# solar_switch.net
KiCad netlist of a schematic drawn in EAGLE
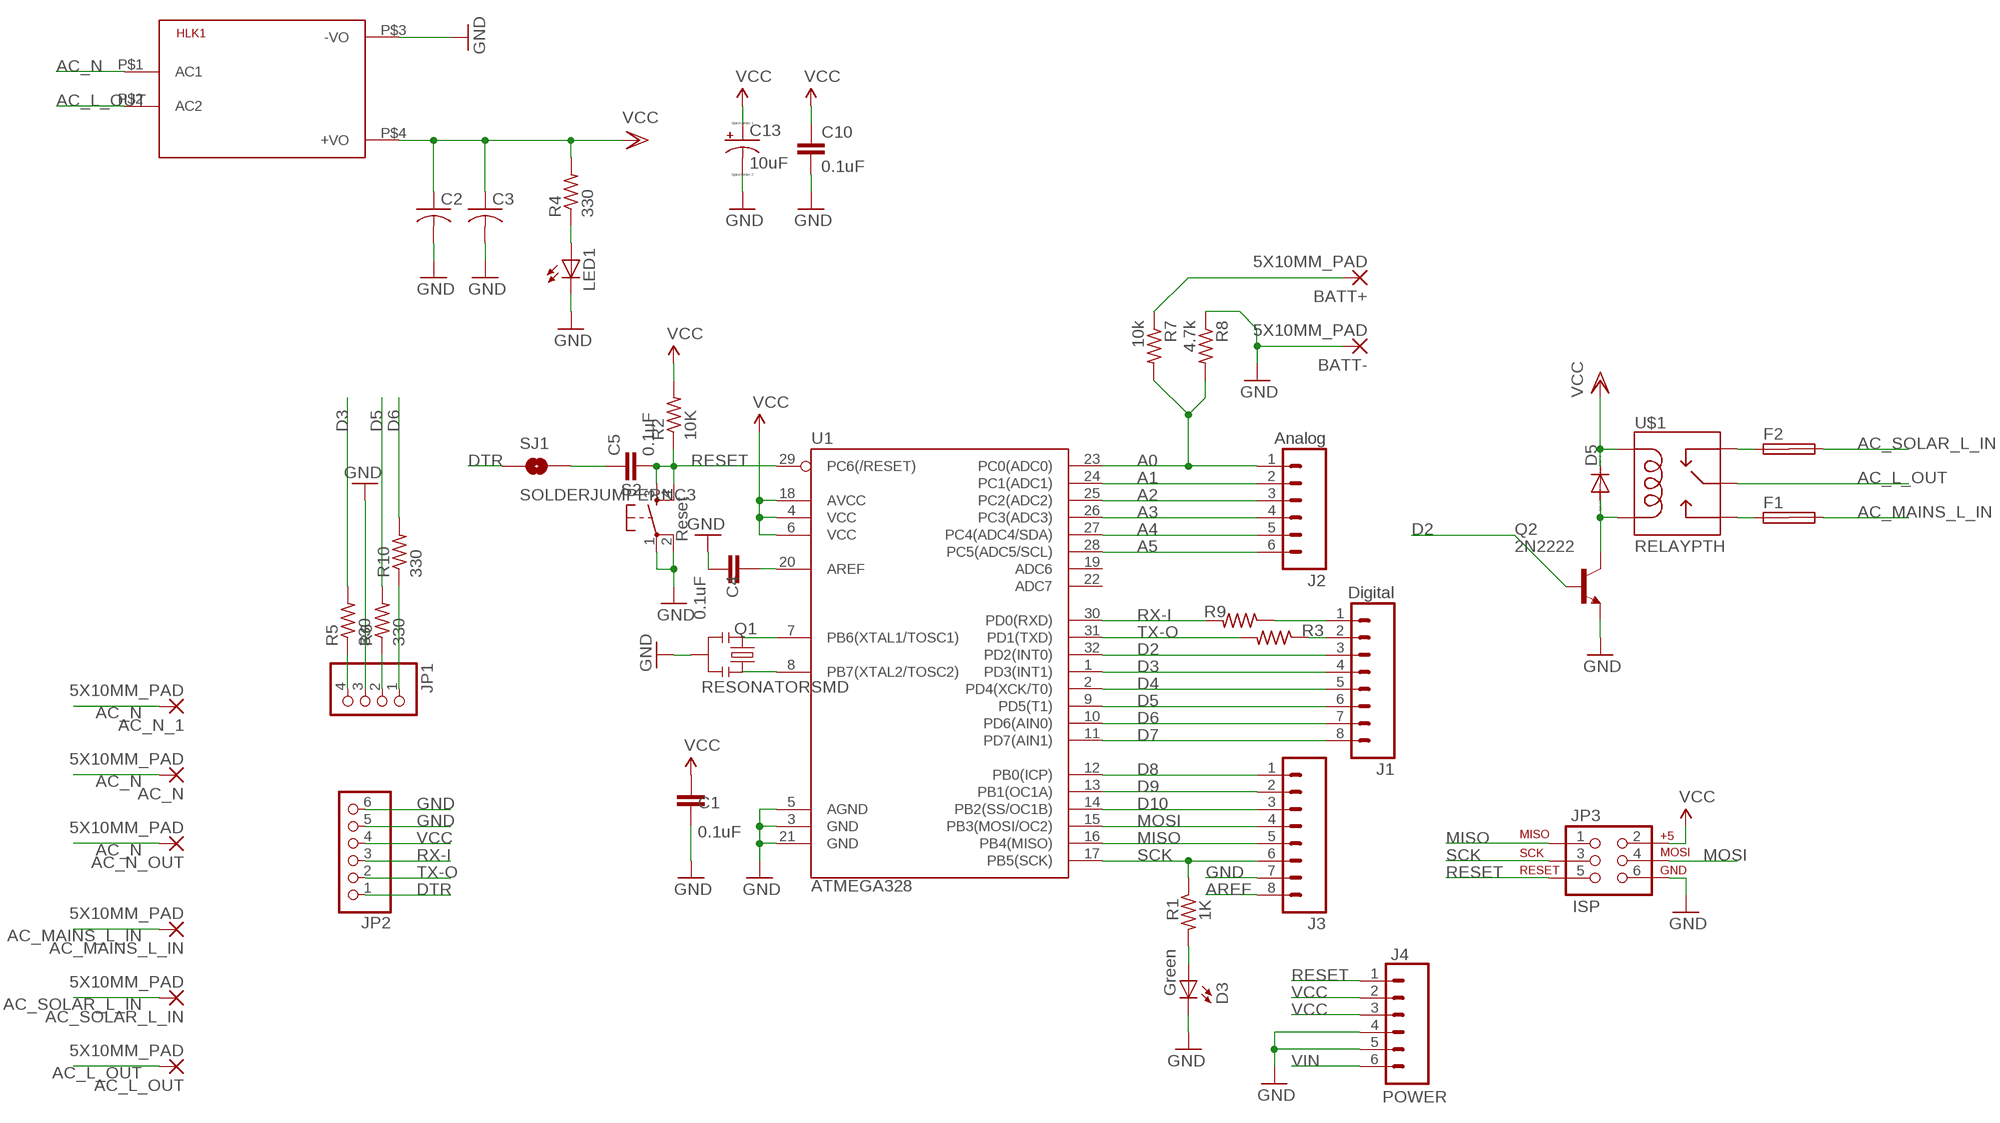
[diagram p0: schematic, sheet 1]

(export (version "E")
  (design (tool "Eeschema 10.0.6"))
  (components
    (comp (ref "AC_L_OUT")
      (value "5X10MM_PAD")
      (footprint "eagle-import:SMD5-10")
      (libsource (lib "eagle-import") (part "5X10MM_PAD"))
    )
    (comp (ref "AC_MAINS_L_IN")
      (value "5X10MM_PAD")
      (footprint "eagle-import:SMD5-10")
      (libsource (lib "eagle-import") (part "5X10MM_PAD"))
    )
    (comp (ref "AC_N")
      (value "5X10MM_PAD")
      (footprint "eagle-import:SMD5-10")
      (libsource (lib "eagle-import") (part "5X10MM_PAD"))
    )
    (comp (ref "AC_N_1")
      (value "5X10MM_PAD")
      (footprint "eagle-import:SMD5-10")
      (libsource (lib "eagle-import") (part "5X10MM_PAD"))
    )
    (comp (ref "AC_N_OUT")
      (value "5X10MM_PAD")
      (footprint "eagle-import:SMD5-10")
      (libsource (lib "eagle-import") (part "5X10MM_PAD"))
    )
    (comp (ref "AC_SOLAR_L_IN")
      (value "5X10MM_PAD")
      (footprint "eagle-import:SMD5-10")
      (libsource (lib "eagle-import") (part "5X10MM_PAD"))
    )
    (comp (ref "BATT+")
      (value "5X10MM_PAD")
      (footprint "eagle-import:SMD5-10")
      (libsource (lib "eagle-import") (part "5X10MM_PAD"))
    )
    (comp (ref "BATT-")
      (value "5X10MM_PAD")
      (footprint "eagle-import:SMD5-10")
      (libsource (lib "eagle-import") (part "5X10MM_PAD"))
    )
    (comp (ref "C1")
      (value "0.1uF")
      (footprint "eagle-import:C0805")
      (libsource (lib "eagle-import") (part "C-EUC0805"))
    )
    (comp (ref "C2")
      (value "C-USC0805K")
      (footprint "eagle-import:C0805K")
      (libsource (lib "eagle-import") (part "C-USC0805K"))
    )
    (comp (ref "C3")
      (value "C-USC0805K")
      (footprint "eagle-import:C0805K")
      (libsource (lib "eagle-import") (part "C-USC0805K"))
    )
    (comp (ref "C4")
      (value "0.1uF")
      (footprint "eagle-import:C0805")
      (libsource (lib "eagle-import") (part "C-EUC0805"))
    )
    (comp (ref "C5")
      (value "0.1uF")
      (footprint "eagle-import:C0805")
      (libsource (lib "eagle-import") (part "C-EUC0805"))
    )
    (comp (ref "C10")
      (value "0.1uF")
      (footprint "eagle-import:C0805")
      (libsource (lib "eagle-import") (part "rcl_334_C-EUC0805"))
    )
    (comp (ref "C13")
      (value "10uF")
      (footprint "eagle-import:PANASONIC_B")
      (libsource (lib "eagle-import") (part "CPOL-USB"))
    )
    (comp (ref "D3")
      (value "Green")
      (footprint "eagle-import:CHIP-LED0805")
      (libsource (lib "eagle-import") (part "LEDCHIP-LED0805"))
    )
    (comp (ref "D5")
      (value "1N4004")
      (footprint "eagle-import:DO41-10")
      (libsource (lib "eagle-import") (part "1N4004"))
    )
    (comp (ref "F1")
      (value "SHKOG")
      (footprint "eagle-import:SHKOG")
      (libsource (lib "eagle-import") (part "SHKOG"))
    )
    (comp (ref "F2")
      (value "SHKOG")
      (footprint "eagle-import:SHKOG")
      (libsource (lib "eagle-import") (part "SHKOG"))
    )
    (comp (ref "HLK1")
      (value "HLK-PM013W")
      (footprint "eagle-import:HLK-PM01")
      (libsource (lib "eagle-import") (part "HLK-PM013W"))
    )
    (comp (ref "J1")
      (value "Digital")
      (footprint "eagle-import:1X08")
      (libsource (lib "eagle-import") (part "M081X08"))
    )
    (comp (ref "J2")
      (value "Analog")
      (footprint "eagle-import:1X06")
      (libsource (lib "eagle-import") (part "M06SIP"))
    )
    (comp (ref "J3")
      (value "M081X08")
      (footprint "eagle-import:1X08")
      (libsource (lib "eagle-import") (part "M081X08"))
    )
    (comp (ref "J4")
      (value "POWER")
      (footprint "eagle-import:1X06")
      (libsource (lib "eagle-import") (part "M06SIP"))
    )
    (comp (ref "JP1")
      (value "PINHD-1X4")
      (footprint "eagle-import:1X04")
      (libsource (lib "eagle-import") (part "PINHD-1X4"))
    )
    (comp (ref "JP2")
      (value "PINHD-1X6")
      (footprint "eagle-import:1X06")
      (libsource (lib "eagle-import") (part "PINHD-1X6"))
    )
    (comp (ref "JP3")
      (value "ISP")
      (footprint "eagle-import:2X3")
      (libsource (lib "eagle-import") (part "AVR_SPI_PRG_6PTH"))
    )
    (comp (ref "LED1")
      (value "LEDCHIPLED_0805")
      (footprint "eagle-import:CHIPLED_0805")
      (libsource (lib "eagle-import") (part "led_LEDCHIPLED_0805"))
    )
    (comp (ref "Q1")
      (value "RESONATORSMD")
      (footprint "eagle-import:RESONATOR-SMD")
      (libsource (lib "eagle-import") (part "RESONATORSMD"))
    )
    (comp (ref "Q2")
      (value "2N2222")
      (footprint "eagle-import:TO18")
      (libsource (lib "eagle-import") (part "2N2222"))
    )
    (comp (ref "R1")
      (value "1K")
      (footprint "eagle-import:R0805")
      (libsource (lib "eagle-import") (part "R-US_R0805"))
    )
    (comp (ref "R2")
      (value "10K")
      (footprint "eagle-import:R0805")
      (libsource (lib "eagle-import") (part "R-US_R0805"))
    )
    (comp (ref "R3")
      (value "220")
      (footprint "eagle-import:R0805")
      (libsource (lib "eagle-import") (part "R-US_R0805"))
    )
    (comp (ref "R4")
      (value "330")
      (footprint "eagle-import:R0805")
      (libsource (lib "eagle-import") (part "R-US_R0805"))
    )
    (comp (ref "R5")
      (value "330")
      (footprint "eagle-import:R0805")
      (libsource (lib "eagle-import") (part "R-US_R0805"))
    )
    (comp (ref "R6")
      (value "330")
      (footprint "eagle-import:R0805")
      (libsource (lib "eagle-import") (part "R-US_R0805"))
    )
    (comp (ref "R7")
      (value "10k")
      (footprint "eagle-import:M0805")
      (libsource (lib "eagle-import") (part "resistor_R-US_M0805"))
    )
    (comp (ref "R8")
      (value "4.7k")
      (footprint "eagle-import:M0805")
      (libsource (lib "eagle-import") (part "resistor_R-US_M0805"))
    )
    (comp (ref "R9")
      (value "220")
      (footprint "eagle-import:R0805")
      (libsource (lib "eagle-import") (part "R-US_R0805"))
    )
    (comp (ref "R10")
      (value "330")
      (footprint "eagle-import:R0805")
      (libsource (lib "eagle-import") (part "R-US_R0805"))
    )
    (comp (ref "S2")
      (value "Reset")
      (footprint "eagle-import:TACTILE_SWITCH_SMD")
      (libsource (lib "eagle-import") (part "TAC_SWITCHSMD"))
    )
    (comp (ref "SJ1")
      (value "SOLDERJUMPERNC3")
      (footprint "eagle-import:SJ_2S-NOTRACE")
      (libsource (lib "eagle-import") (part "SOLDERJUMPERNC2"))
    )
    (comp (ref "U$1")
      (value "RELAYPTH")
      (footprint "eagle-import:SRD-05VDC-SL-C")
      (libsource (lib "eagle-import") (part "RELAYPTH"))
    )
    (comp (ref "U1")
      (value "ATMEGA328")
      (footprint "eagle-import:TQFP32-08")
      (libsource (lib "eagle-import") (part "ATMEGA168"))
    )
  )
  (nets
    (net (code "1") (name "/A0") (class "Default")
      (node (ref "J2") (pin "1") (pinfunction "1_1") (pintype "passive"))
      (node (ref "R7") (pin "2") (pinfunction "2_2") (pintype "passive"))
      (node (ref "R8") (pin "2") (pinfunction "2_2") (pintype "passive"))
      (node (ref "U1") (pin "23") (pinfunction "PC0(ADC0)_23") (pintype "bidirectional"))
    )
    (net (code "2") (name "/A1") (class "Default")
      (node (ref "J2") (pin "2") (pinfunction "2_2") (pintype "passive"))
      (node (ref "U1") (pin "24") (pinfunction "PC1(ADC1)_24") (pintype "bidirectional"))
    )
    (net (code "3") (name "/A2") (class "Default")
      (node (ref "J2") (pin "3") (pinfunction "3_3") (pintype "passive"))
      (node (ref "U1") (pin "25") (pinfunction "PC2(ADC2)_25") (pintype "bidirectional"))
    )
    (net (code "4") (name "/A3") (class "Default")
      (node (ref "J2") (pin "4") (pinfunction "4_4") (pintype "passive"))
      (node (ref "U1") (pin "26") (pinfunction "PC3(ADC3)_26") (pintype "bidirectional"))
    )
    (net (code "5") (name "/A4") (class "Default")
      (node (ref "J2") (pin "5") (pinfunction "5_5") (pintype "passive"))
      (node (ref "U1") (pin "27") (pinfunction "PC4(ADC4/SDA)_27") (pintype "bidirectional"))
    )
    (net (code "6") (name "/A5") (class "Default")
      (node (ref "J2") (pin "6") (pinfunction "6_6") (pintype "passive"))
      (node (ref "U1") (pin "28") (pinfunction "PC5(ADC5/SCL)_28") (pintype "bidirectional"))
    )
    (net (code "7") (name "/AC_L_OUT") (class "Default")
      (node (ref "AC_L_OUT") (pin "1") (pinfunction "P_1") (pintype "passive"))
      (node (ref "HLK1") (pin "P$2") (pinfunction "AC2_P$2") (pintype "bidirectional"))
      (node (ref "U$1") (pin "SWCOMMON") (pinfunction "SWCOMMON_SWCOMMON") (pintype "bidirectional"))
    )
    (net (code "8") (name "/AC_MAINS_L_IN") (class "Default")
      (node (ref "AC_MAINS_L_IN") (pin "1") (pinfunction "P_1") (pintype "passive"))
      (node (ref "F1") (pin "2A") (pinfunction "2A_2A") (pintype "passive"))
    )
    (net (code "9") (name "/AC_N") (class "Default")
      (node (ref "AC_N") (pin "1") (pinfunction "P_1") (pintype "passive"))
      (node (ref "AC_N_1") (pin "1") (pinfunction "P_1") (pintype "passive"))
      (node (ref "AC_N_OUT") (pin "1") (pinfunction "P_1") (pintype "passive"))
      (node (ref "HLK1") (pin "P$1") (pinfunction "AC1_P$1") (pintype "bidirectional"))
    )
    (net (code "10") (name "/AC_SOLAR_L_IN") (class "Default")
      (node (ref "AC_SOLAR_L_IN") (pin "1") (pinfunction "P_1") (pintype "passive"))
      (node (ref "F2") (pin "2A") (pinfunction "2A_2A") (pintype "passive"))
    )
    (net (code "11") (name "/AREF") (class "Default")
      (node (ref "C4") (pin "2") (pinfunction "2_2") (pintype "passive"))
      (node (ref "J3") (pin "8") (pinfunction "8_8") (pintype "passive"))
      (node (ref "U1") (pin "20") (pinfunction "AREF_20") (pintype "bidirectional"))
    )
    (net (code "12") (name "/D2") (class "Default")
      (node (ref "J1") (pin "3") (pinfunction "3_3") (pintype "passive"))
      (node (ref "Q2") (pin "2") (pinfunction "B_2") (pintype "passive"))
      (node (ref "U1") (pin "32") (pinfunction "PD2(INT0)_32") (pintype "bidirectional"))
    )
    (net (code "13") (name "/D3") (class "Default")
      (node (ref "J1") (pin "4") (pinfunction "4_4") (pintype "passive"))
      (node (ref "R5") (pin "2") (pinfunction "2_2") (pintype "passive"))
      (node (ref "U1") (pin "1") (pinfunction "PD3(INT1)_1") (pintype "bidirectional"))
    )
    (net (code "14") (name "/D4") (class "Default")
      (node (ref "J1") (pin "5") (pinfunction "5_5") (pintype "passive"))
      (node (ref "U1") (pin "2") (pinfunction "PD4(XCK/T0)_2") (pintype "bidirectional"))
    )
    (net (code "15") (name "/D5") (class "Default")
      (node (ref "J1") (pin "6") (pinfunction "6_6") (pintype "passive"))
      (node (ref "R6") (pin "2") (pinfunction "2_2") (pintype "passive"))
      (node (ref "U1") (pin "9") (pinfunction "PD5(T1)_9") (pintype "bidirectional"))
    )
    (net (code "16") (name "/D6") (class "Default")
      (node (ref "J1") (pin "7") (pinfunction "7_7") (pintype "passive"))
      (node (ref "R10") (pin "2") (pinfunction "2_2") (pintype "passive"))
      (node (ref "U1") (pin "10") (pinfunction "PD6(AIN0)_10") (pintype "bidirectional"))
    )
    (net (code "17") (name "/D7") (class "Default")
      (node (ref "J1") (pin "8") (pinfunction "8_8") (pintype "passive"))
      (node (ref "U1") (pin "11") (pinfunction "PD7(AIN1)_11") (pintype "bidirectional"))
    )
    (net (code "18") (name "/D8") (class "Default")
      (node (ref "J3") (pin "1") (pinfunction "1_1") (pintype "passive"))
      (node (ref "U1") (pin "12") (pinfunction "PB0(ICP)_12") (pintype "bidirectional"))
    )
    (net (code "19") (name "/D9") (class "Default")
      (node (ref "J3") (pin "2") (pinfunction "2_2") (pintype "passive"))
      (node (ref "U1") (pin "13") (pinfunction "PB1(OC1A)_13") (pintype "bidirectional"))
    )
    (net (code "20") (name "/D10") (class "Default")
      (node (ref "J3") (pin "3") (pinfunction "3_3") (pintype "passive"))
      (node (ref "U1") (pin "14") (pinfunction "PB2(SS/OC1B)_14") (pintype "bidirectional"))
    )
    (net (code "21") (name "/DTR") (class "Default")
      (node (ref "JP2") (pin "1") (pinfunction "1_1") (pintype "passive"))
      (node (ref "SJ1") (pin "1") (pinfunction "1_1") (pintype "passive"))
    )
    (net (code "22") (name "/MISO") (class "Default")
      (node (ref "J3") (pin "5") (pinfunction "5_5") (pintype "passive"))
      (node (ref "JP3") (pin "1") (pinfunction "1_1") (pintype "passive"))
      (node (ref "U1") (pin "16") (pinfunction "PB4(MISO)_16") (pintype "bidirectional"))
    )
    (net (code "23") (name "/MOSI") (class "Default")
      (node (ref "J3") (pin "4") (pinfunction "4_4") (pintype "passive"))
      (node (ref "JP3") (pin "4") (pinfunction "4_4") (pintype "passive"))
      (node (ref "U1") (pin "15") (pinfunction "PB3(MOSI/OC2)_15") (pintype "bidirectional"))
    )
    (net (code "24") (name "/RESET") (class "Default")
      (node (ref "C5") (pin "2") (pinfunction "2_2") (pintype "passive"))
      (node (ref "J4") (pin "1") (pinfunction "1_1") (pintype "passive"))
      (node (ref "JP3") (pin "5") (pinfunction "5_5") (pintype "passive"))
      (node (ref "R2") (pin "1") (pinfunction "1_1") (pintype "passive"))
      (node (ref "S2") (pin "3") (pinfunction "3_3") (pintype "passive"))
      (node (ref "S2") (pin "4") (pinfunction "4_4") (pintype "passive"))
      (node (ref "U1") (pin "29") (pinfunction "PC6(/RESET)_29") (pintype "bidirectional"))
    )
    (net (code "25") (name "/RX-I") (class "Default")
      (node (ref "JP2") (pin "3") (pinfunction "3_3") (pintype "passive"))
      (node (ref "R9") (pin "2") (pinfunction "2_2") (pintype "passive"))
      (node (ref "U1") (pin "30") (pinfunction "PD0(RXD)_30") (pintype "bidirectional"))
    )
    (net (code "26") (name "/SCK") (class "Default")
      (node (ref "J3") (pin "6") (pinfunction "6_6") (pintype "passive"))
      (node (ref "JP3") (pin "3") (pinfunction "3_3") (pintype "passive"))
      (node (ref "R1") (pin "1") (pinfunction "1_1") (pintype "passive"))
      (node (ref "U1") (pin "17") (pinfunction "PB5(SCK)_17") (pintype "bidirectional"))
    )
    (net (code "27") (name "/TX-O") (class "Default")
      (node (ref "JP2") (pin "2") (pinfunction "2_2") (pintype "passive"))
      (node (ref "R3") (pin "2") (pinfunction "2_2") (pintype "passive"))
      (node (ref "U1") (pin "31") (pinfunction "PD1(TXD)_31") (pintype "bidirectional"))
    )
    (net (code "28") (name "/VIN") (class "Default")
      (node (ref "J4") (pin "6") (pinfunction "6_6") (pintype "passive"))
    )
    (net (code "29") (name "GND") (class "Default")
      (node (ref "BATT-") (pin "1") (pinfunction "P_1") (pintype "passive"))
      (node (ref "C1") (pin "1") (pinfunction "1_1") (pintype "passive"))
      (node (ref "C10") (pin "2") (pinfunction "2_2") (pintype "passive"))
      (node (ref "C13") (pin "-") (pinfunction "-_-") (pintype "passive"))
      (node (ref "C2") (pin "2") (pinfunction "2_2") (pintype "passive"))
      (node (ref "C3") (pin "2") (pinfunction "2_2") (pintype "passive"))
      (node (ref "C4") (pin "1") (pinfunction "1_1") (pintype "passive"))
      (node (ref "D3") (pin "C") (pinfunction "C_C") (pintype "passive"))
      (node (ref "HLK1") (pin "P$3") (pinfunction "-VO_P$3") (pintype "bidirectional"))
      (node (ref "J3") (pin "7") (pinfunction "7_7") (pintype "passive"))
      (node (ref "J4") (pin "4") (pinfunction "4_4") (pintype "passive"))
      (node (ref "J4") (pin "5") (pinfunction "5_5") (pintype "passive"))
      (node (ref "JP1") (pin "3") (pinfunction "3_3") (pintype "passive"))
      (node (ref "JP2") (pin "5") (pinfunction "5_5") (pintype "passive"))
      (node (ref "JP2") (pin "6") (pinfunction "6_6") (pintype "passive"))
      (node (ref "JP3") (pin "6") (pinfunction "6_6") (pintype "passive"))
      (node (ref "LED1") (pin "C") (pinfunction "C_C") (pintype "passive"))
      (node (ref "Q1") (pin "2") (pinfunction "2_2") (pintype "passive"))
      (node (ref "Q2") (pin "1") (pinfunction "E_1") (pintype "passive"))
      (node (ref "R8") (pin "1") (pinfunction "1_1") (pintype "passive"))
      (node (ref "S2") (pin "1") (pinfunction "1_1") (pintype "passive"))
      (node (ref "S2") (pin "2") (pinfunction "2_2") (pintype "passive"))
      (node (ref "U1") (pin "21") (pinfunction "GND_21") (pintype "bidirectional"))
      (node (ref "U1") (pin "3") (pinfunction "GND_3") (pintype "bidirectional"))
      (node (ref "U1") (pin "5") (pinfunction "AGND_5") (pintype "bidirectional"))
    )
    (net (code "30") (name "Net-(BATT+-P)") (class "Default")
      (node (ref "BATT+") (pin "1") (pinfunction "P_1") (pintype "passive"))
      (node (ref "R7") (pin "1") (pinfunction "1_1") (pintype "passive"))
    )
    (net (code "31") (name "Net-(C5-Pad1)") (class "Default")
      (node (ref "C5") (pin "1") (pinfunction "1_1") (pintype "passive"))
      (node (ref "SJ1") (pin "2") (pinfunction "2_2") (pintype "passive"))
    )
    (net (code "32") (name "Net-(D3-PadA)") (class "Default")
      (node (ref "D3") (pin "A") (pinfunction "A_A") (pintype "passive"))
      (node (ref "R1") (pin "2") (pinfunction "2_2") (pintype "passive"))
    )
    (net (code "33") (name "Net-(F1-Pad1A)") (class "Default")
      (node (ref "F1") (pin "1A") (pinfunction "1A_1A") (pintype "passive"))
      (node (ref "U$1") (pin "SWOPEN") (pinfunction "SWOPEN_SWOPEN") (pintype "bidirectional"))
    )
    (net (code "34") (name "Net-(J1-Pad1)") (class "Default")
      (node (ref "J1") (pin "1") (pinfunction "1_1") (pintype "passive"))
      (node (ref "R9") (pin "1") (pinfunction "1_1") (pintype "passive"))
    )
    (net (code "35") (name "Net-(J1-Pad2)") (class "Default")
      (node (ref "J1") (pin "2") (pinfunction "2_2") (pintype "passive"))
      (node (ref "R3") (pin "1") (pinfunction "1_1") (pintype "passive"))
    )
    (net (code "36") (name "Net-(JP1-Pad1)") (class "Default")
      (node (ref "JP1") (pin "1") (pinfunction "1_1") (pintype "passive"))
      (node (ref "R10") (pin "1") (pinfunction "1_1") (pintype "passive"))
    )
    (net (code "37") (name "Net-(JP1-Pad2)") (class "Default")
      (node (ref "JP1") (pin "2") (pinfunction "2_2") (pintype "passive"))
      (node (ref "R6") (pin "1") (pinfunction "1_1") (pintype "passive"))
    )
    (net (code "38") (name "Net-(JP1-Pad4)") (class "Default")
      (node (ref "JP1") (pin "4") (pinfunction "4_4") (pintype "passive"))
      (node (ref "R5") (pin "1") (pinfunction "1_1") (pintype "passive"))
    )
    (net (code "39") (name "Net-(LED1-PadA)") (class "Default")
      (node (ref "LED1") (pin "A") (pinfunction "A_A") (pintype "passive"))
      (node (ref "R4") (pin "1") (pinfunction "1_1") (pintype "passive"))
    )
    (net (code "40") (name "Net-(Q2-C)") (class "Default")
      (node (ref "D5") (pin "A") (pinfunction "A_A") (pintype "passive"))
      (node (ref "Q2") (pin "3") (pinfunction "C_3") (pintype "passive"))
      (node (ref "U$1") (pin "COIL0") (pinfunction "COIL0_COIL0") (pintype "bidirectional"))
    )
    (net (code "41") (name "Net-(U$1-SWCLOSE)") (class "Default")
      (node (ref "F2") (pin "1A") (pinfunction "1A_1A") (pintype "passive"))
      (node (ref "U$1") (pin "SWCLOSED") (pinfunction "SWCLOSE_SWCLOSED") (pintype "bidirectional"))
    )
    (net (code "42") (name "Net-(U1-PB6(XTAL1{slash}TOSC1))") (class "Default")
      (node (ref "Q1") (pin "3") (pinfunction "3_3") (pintype "passive"))
      (node (ref "U1") (pin "7") (pinfunction "PB6(XTAL1/TOSC1)_7") (pintype "bidirectional"))
    )
    (net (code "43") (name "Net-(U1-PB7(XTAL2{slash}TOSC2))") (class "Default")
      (node (ref "Q1") (pin "1") (pinfunction "1_1") (pintype "passive"))
      (node (ref "U1") (pin "8") (pinfunction "PB7(XTAL2/TOSC2)_8") (pintype "bidirectional"))
    )
    (net (code "44") (name "VCC") (class "Default")
      (node (ref "C1") (pin "2") (pinfunction "2_2") (pintype "passive"))
      (node (ref "C10") (pin "1") (pinfunction "1_1") (pintype "passive"))
      (node (ref "C13") (pin "+") (pinfunction "+_+") (pintype "passive"))
      (node (ref "C2") (pin "1") (pinfunction "1_1") (pintype "passive"))
      (node (ref "C3") (pin "1") (pinfunction "1_1") (pintype "passive"))
      (node (ref "D5") (pin "C") (pinfunction "C_C") (pintype "passive"))
      (node (ref "HLK1") (pin "P$4") (pinfunction "+VO_P$4") (pintype "bidirectional"))
      (node (ref "J4") (pin "2") (pinfunction "2_2") (pintype "passive"))
      (node (ref "J4") (pin "3") (pinfunction "3_3") (pintype "passive"))
      (node (ref "JP2") (pin "4") (pinfunction "4_4") (pintype "passive"))
      (node (ref "JP3") (pin "2") (pinfunction "2_2") (pintype "passive"))
      (node (ref "R2") (pin "2") (pinfunction "2_2") (pintype "passive"))
      (node (ref "R4") (pin "2") (pinfunction "2_2") (pintype "passive"))
      (node (ref "U$1") (pin "COIL1") (pinfunction "COIL1_COIL1") (pintype "bidirectional"))
      (node (ref "U1") (pin "18") (pinfunction "AVCC_18") (pintype "bidirectional"))
      (node (ref "U1") (pin "4") (pinfunction "VCC_4") (pintype "bidirectional"))
      (node (ref "U1") (pin "6") (pinfunction "VCC_6") (pintype "bidirectional"))
    )
    (net (code "45") (name "unconnected-(F1-Pad1B)") (class "Default")
      (node (ref "F1") (pin "1B") (pinfunction "1B_1B") (pintype "passive"))
    )
    (net (code "46") (name "unconnected-(F1-Pad2B)") (class "Default")
      (node (ref "F1") (pin "2B") (pinfunction "2B_2B") (pintype "passive"))
    )
    (net (code "47") (name "unconnected-(F2-Pad1B)") (class "Default")
      (node (ref "F2") (pin "1B") (pinfunction "1B_1B") (pintype "passive"))
    )
    (net (code "48") (name "unconnected-(F2-Pad2B)") (class "Default")
      (node (ref "F2") (pin "2B") (pinfunction "2B_2B") (pintype "passive"))
    )
    (net (code "49") (name "unconnected-(U1-ADC6-Pad19)") (class "Default")
      (node (ref "U1") (pin "19") (pinfunction "ADC6_19") (pintype "bidirectional"))
    )
    (net (code "50") (name "unconnected-(U1-ADC7-Pad22)") (class "Default")
      (node (ref "U1") (pin "22") (pinfunction "ADC7_22") (pintype "bidirectional"))
    )
  )
)
